# 4_Shutdown.net
KiCad netlist of a schematic drawn in Altium Designer
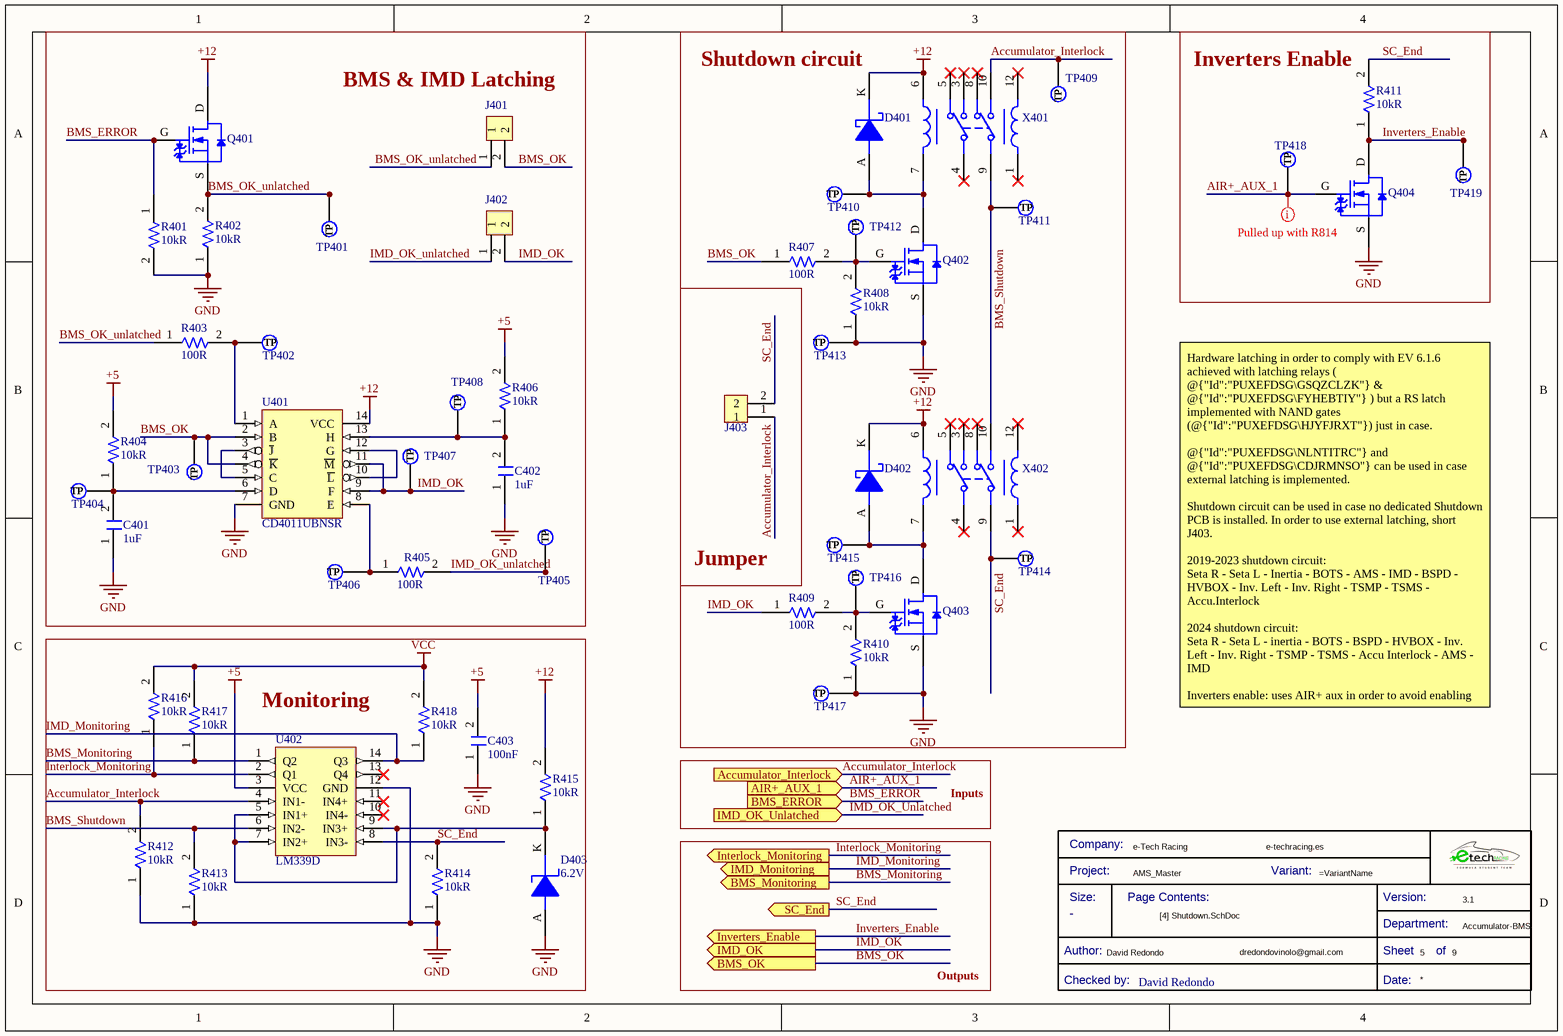
[diagram p0: [4] Shutdown.SchDoc]

(export (version "E")
  (design (tool "Eeschema 10.0.6"))
  (components
    (comp (ref "C401")
      (value "885012207103")
      (footprint "C0805FNPC-R")
      (fields
        (field (name "TOLERANCE") "10%")
        (field (name "CAPACITANCE") "1uF")
        (field (name ".CREATOR") "GP")
      )
      (libsource (lib "Passives") (part "C1u-50V-0805FNPC-X7R"))
    )
    (comp (ref "C402")
      (value "885012207103")
      (footprint "C0805FNPC-R")
      (fields
        (field (name "TOLERANCE") "10%")
        (field (name "CAPACITANCE") "1uF")
        (field (name ".CREATOR") "GP")
      )
      (libsource (lib "Passives") (part "C1u-50V-0805FNPC-X7R"))
    )
    (comp (ref "C403")
      (value "885012207098")
      (footprint "C0805FNPC-R")
      (description "Cap, 0.1ΜF, 50V, 10%, X7R, 0805")
      (fields
        (field (name "TOLERANCE") "10%")
        (field (name "CAPACITANCE") "100nF")
        (field (name ".CREATOR") "DR")
      )
      (libsource (lib "Passives") (part "C100n-50V-0805FNPC-X7R"))
    )
    (comp (ref "D401")
      (value "MBR0530")
      (footprint "DSC-SOD123")
      (description "VR=30V IF=500mA 30pF P=410mW")
      (fields (field (name ".CREATOR") "GP"))
      (libsource (lib "Filter components") (part "DSC-0.5/30-SOD123"))
    )
    (comp (ref "D402")
      (value "MBR0530")
      (footprint "DSC-SOD123")
      (description "VR=30V IF=500mA 30pF P=410mW")
      (fields (field (name ".CREATOR") "GP"))
      (libsource (lib "Filter components") (part "DSC-0.5/30-SOD123"))
    )
    (comp (ref "D403")
      (value "BZG05C6V2-E3-TR")
      (footprint "DZ-6.2V-DO-214AC")
      (description "BZG05C Series 6.2 V 200 mA Surface Mount Zener Diode - DO-214AC")
      (fields
        (field (name "TOLERANCE") "5%")
        (field (name "ZENER VOLTAGE") "6.2V")
        (field (name ".CREATOR") "DO")
      )
      (libsource (lib "Semiconductor") (part "DZ-6.2V-DO-214AC"))
    )
    (comp (ref "J401")
      (value "61300211121")
      (footprint "J_Pinheader_1x2")
      (description "CONN HEADER 2 POS 2.54")
      (fields (field (name "MANUFACTURER") "Molex") (field (name ".CREATOR") "GP"))
      (libsource (lib "Electromechanical") (part "J_Jumper"))
    )
    (comp (ref "J402")
      (value "61300211121")
      (footprint "J_Pinheader_1x2")
      (description "CONN HEADER 2 POS 2.54")
      (fields (field (name "MANUFACTURER") "Molex") (field (name ".CREATOR") "GP"))
      (libsource (lib "Electromechanical") (part "J_Jumper"))
    )
    (comp (ref "J403")
      (value "61300211121")
      (footprint "J_Pinheader_1x2")
      (description "CONN HEADER 2 POS 2.54")
      (fields (field (name "MANUFACTURER") "Molex") (field (name ".CREATOR") "GP"))
      (libsource (lib "") (part "J_Jumper_1"))
    )
    (comp (ref "Q401")
      (value "CPH3455-TL-H")
      (footprint "TRT-NCH-3/35-CPH")
      (description "CPH3455-TL-H N-channel MOSFET Transistor; 3 A; 35 V; 3-Pin CPH")
      (fields (field (name "MANUFACTURER") "ON Semiconductor") (field (name ".CREATOR") "GP"))
      (libsource (lib "Semiconductor") (part "TRT-NCH-3/35-CPH"))
    )
    (comp (ref "Q402")
      (value "CPH3455-TL-H")
      (footprint "TRT-NCH-3/35-CPH")
      (description "CPH3455-TL-H N-channel MOSFET Transistor; 3 A; 35 V; 3-Pin CPH")
      (fields (field (name "MANUFACTURER") "ON Semiconductor") (field (name ".CREATOR") "GP"))
      (libsource (lib "Semiconductor") (part "TRT-NCH-3/35-CPH"))
    )
    (comp (ref "Q403")
      (value "CPH3455-TL-H")
      (footprint "TRT-NCH-3/35-CPH")
      (description "CPH3455-TL-H N-channel MOSFET Transistor; 3 A; 35 V; 3-Pin CPH")
      (fields (field (name "MANUFACTURER") "ON Semiconductor") (field (name ".CREATOR") "GP"))
      (libsource (lib "Semiconductor") (part "TRT-NCH-3/35-CPH"))
    )
    (comp (ref "Q404")
      (value "CPH3455-TL-H")
      (footprint "TRT-NCH-3/35-CPH")
      (description "CPH3455-TL-H N-channel MOSFET Transistor; 3 A; 35 V; 3-Pin CPH")
      (fields (field (name "MANUFACTURER") "ON Semiconductor") (field (name ".CREATOR") "GP"))
      (libsource (lib "Semiconductor") (part "TRT-NCH-3/35-CPH"))
    )
    (comp (ref "R401")
      (value "CR0805-JW-103ELF")
      (footprint "R0805FTK")
      (fields
        (field (name "TOLERANCE") "5%")
        (field (name "RESISTANCE") "10kR")
        (field (name ".CREATOR") "DR")
      )
      (libsource (lib "Passives") (part "R10k-0805FTK"))
    )
    (comp (ref "R402")
      (value "CR0805-JW-103ELF")
      (footprint "R0805FTK")
      (fields
        (field (name "TOLERANCE") "5%")
        (field (name "RESISTANCE") "10kR")
        (field (name ".CREATOR") "DR")
      )
      (libsource (lib "Passives") (part "R10k-0805FTK"))
    )
    (comp (ref "R403")
      (value "CR0805-FX-1000ELF")
      (footprint "R0805FTK")
      (description "Res Thick Film 0805 100 Ohm 1% 1/8W ±100ppm/°C Molded SMD SMD Paper Tape on Plastic Reel")
      (fields
        (field (name "TOLERANCE") "1%")
        (field (name "RESISTANCE") "100R")
        (field (name ".CREATOR") "DR")
      )
      (libsource (lib "Passives") (part "R100-0805FTK"))
    )
    (comp (ref "R404")
      (value "CR0805-JW-103ELF")
      (footprint "R0805FTK")
      (fields
        (field (name "TOLERANCE") "5%")
        (field (name "RESISTANCE") "10kR")
        (field (name ".CREATOR") "DR")
      )
      (libsource (lib "Passives") (part "R10k-0805FTK"))
    )
    (comp (ref "R405")
      (value "CR0805-FX-1000ELF")
      (footprint "R0805FTK")
      (description "Res Thick Film 0805 100 Ohm 1% 1/8W ±100ppm/°C Molded SMD SMD Paper Tape on Plastic Reel")
      (fields
        (field (name "TOLERANCE") "1%")
        (field (name "RESISTANCE") "100R")
        (field (name ".CREATOR") "DR")
      )
      (libsource (lib "Passives") (part "R100-0805FTK"))
    )
    (comp (ref "R406")
      (value "CR0805-JW-103ELF")
      (footprint "R0805FTK")
      (fields
        (field (name "TOLERANCE") "5%")
        (field (name "RESISTANCE") "10kR")
        (field (name ".CREATOR") "DR")
      )
      (libsource (lib "Passives") (part "R10k-0805FTK"))
    )
    (comp (ref "R407")
      (value "CR0805-FX-1000ELF")
      (footprint "R0805FTK")
      (description "Res Thick Film 0805 100 Ohm 1% 1/8W ±100ppm/°C Molded SMD SMD Paper Tape on Plastic Reel")
      (fields
        (field (name "TOLERANCE") "1%")
        (field (name "RESISTANCE") "100R")
        (field (name ".CREATOR") "DR")
      )
      (libsource (lib "Passives") (part "R100-0805FTK"))
    )
    (comp (ref "R408")
      (value "CR0805-JW-103ELF")
      (footprint "R0805FTK")
      (fields
        (field (name "TOLERANCE") "5%")
        (field (name "RESISTANCE") "10kR")
        (field (name ".CREATOR") "DR")
      )
      (libsource (lib "Passives") (part "R10k-0805FTK"))
    )
    (comp (ref "R409")
      (value "CR0805-FX-1000ELF")
      (footprint "R0805FTK")
      (description "Res Thick Film 0805 100 Ohm 1% 1/8W ±100ppm/°C Molded SMD SMD Paper Tape on Plastic Reel")
      (fields
        (field (name "TOLERANCE") "1%")
        (field (name "RESISTANCE") "100R")
        (field (name ".CREATOR") "DR")
      )
      (libsource (lib "Passives") (part "R100-0805FTK"))
    )
    (comp (ref "R410")
      (value "CR0805-JW-103ELF")
      (footprint "R0805FTK")
      (fields
        (field (name "TOLERANCE") "5%")
        (field (name "RESISTANCE") "10kR")
        (field (name ".CREATOR") "DR")
      )
      (libsource (lib "Passives") (part "R10k-0805FTK"))
    )
    (comp (ref "R411")
      (value "CR0805-JW-103ELF")
      (footprint "R0805FTK")
      (fields
        (field (name "TOLERANCE") "5%")
        (field (name "RESISTANCE") "10kR")
        (field (name ".CREATOR") "DR")
      )
      (libsource (lib "Passives") (part "R10k-0805FTK"))
    )
    (comp (ref "R412")
      (value "CR0805-JW-103ELF")
      (footprint "R0805FTK")
      (fields
        (field (name "TOLERANCE") "5%")
        (field (name "RESISTANCE") "10kR")
        (field (name ".CREATOR") "DR")
      )
      (libsource (lib "Passives") (part "R10k-0805FTK"))
    )
    (comp (ref "R413")
      (value "CR0805-JW-103ELF")
      (footprint "R0805FTK")
      (fields
        (field (name "TOLERANCE") "5%")
        (field (name "RESISTANCE") "10kR")
        (field (name ".CREATOR") "DR")
      )
      (libsource (lib "Passives") (part "R10k-0805FTK"))
    )
    (comp (ref "R414")
      (value "CR0805-JW-103ELF")
      (footprint "R0805FTK")
      (fields
        (field (name "TOLERANCE") "5%")
        (field (name "RESISTANCE") "10kR")
        (field (name ".CREATOR") "DR")
      )
      (libsource (lib "Passives") (part "R10k-0805FTK"))
    )
    (comp (ref "R415")
      (value "CR0805-JW-103ELF")
      (footprint "R0805FTK")
      (fields
        (field (name "TOLERANCE") "5%")
        (field (name "RESISTANCE") "10kR")
        (field (name ".CREATOR") "DR")
      )
      (libsource (lib "Passives") (part "R10k-0805FTK"))
    )
    (comp (ref "R416")
      (value "CR0805-JW-103ELF")
      (footprint "R0805FTK")
      (fields
        (field (name "TOLERANCE") "5%")
        (field (name "RESISTANCE") "10kR")
        (field (name ".CREATOR") "DR")
      )
      (libsource (lib "Passives") (part "R10k-0805FTK"))
    )
    (comp (ref "R417")
      (value "CR0805-JW-103ELF")
      (footprint "R0805FTK")
      (fields
        (field (name "TOLERANCE") "5%")
        (field (name "RESISTANCE") "10kR")
        (field (name ".CREATOR") "DR")
      )
      (libsource (lib "Passives") (part "R10k-0805FTK"))
    )
    (comp (ref "R418")
      (value "CR0805-JW-103ELF")
      (footprint "R0805FTK")
      (fields
        (field (name "TOLERANCE") "5%")
        (field (name "RESISTANCE") "10kR")
        (field (name ".CREATOR") "DR")
      )
      (libsource (lib "Passives") (part "R10k-0805FTK"))
    )
    (comp (ref "TP401")
      (value "TestPoint")
      (footprint "TestPoint")
      (description "Test Point 1x1 mm")
      (fields (field (name ".CREATOR") "GP") (field (name ".PCBCHECK") "GP") (field (name ".SCHCHECK") "GP"))
      (libsource (lib "e-Tech_Racing") (part "TestPoint"))
    )
    (comp (ref "TP402")
      (value "TestPoint")
      (footprint "TestPoint")
      (description "Test Point 1x1 mm")
      (fields (field (name ".CREATOR") "GP") (field (name ".PCBCHECK") "GP") (field (name ".SCHCHECK") "GP"))
      (libsource (lib "e-Tech_Racing") (part "TestPoint"))
    )
    (comp (ref "TP403")
      (value "TestPoint")
      (footprint "TestPoint")
      (description "Test Point 1x1 mm")
      (fields (field (name ".CREATOR") "GP") (field (name ".PCBCHECK") "GP") (field (name ".SCHCHECK") "GP"))
      (libsource (lib "e-Tech_Racing") (part "TestPoint"))
    )
    (comp (ref "TP404")
      (value "TestPoint")
      (footprint "TestPoint")
      (description "Test Point 1x1 mm")
      (fields (field (name ".CREATOR") "GP") (field (name ".PCBCHECK") "GP") (field (name ".SCHCHECK") "GP"))
      (libsource (lib "e-Tech_Racing") (part "TestPoint"))
    )
    (comp (ref "TP405")
      (value "TestPoint")
      (footprint "TestPoint")
      (description "Test Point 1x1 mm")
      (fields (field (name ".CREATOR") "GP") (field (name ".PCBCHECK") "GP") (field (name ".SCHCHECK") "GP"))
      (libsource (lib "e-Tech_Racing") (part "TestPoint"))
    )
    (comp (ref "TP406")
      (value "TestPoint")
      (footprint "TestPoint")
      (description "Test Point 1x1 mm")
      (fields (field (name ".CREATOR") "GP") (field (name ".PCBCHECK") "GP") (field (name ".SCHCHECK") "GP"))
      (libsource (lib "e-Tech_Racing") (part "TestPoint"))
    )
    (comp (ref "TP407")
      (value "TestPoint")
      (footprint "TestPoint")
      (description "Test Point 1x1 mm")
      (fields (field (name ".CREATOR") "GP") (field (name ".PCBCHECK") "GP") (field (name ".SCHCHECK") "GP"))
      (libsource (lib "e-Tech_Racing") (part "TestPoint"))
    )
    (comp (ref "TP408")
      (value "TestPoint")
      (footprint "TestPoint")
      (description "Test Point 1x1 mm")
      (fields (field (name ".CREATOR") "GP") (field (name ".PCBCHECK") "GP") (field (name ".SCHCHECK") "GP"))
      (libsource (lib "e-Tech_Racing") (part "TestPoint"))
    )
    (comp (ref "TP409")
      (value "TestPoint")
      (footprint "TestPoint")
      (description "Test Point 1x1 mm")
      (fields (field (name ".CREATOR") "GP") (field (name ".PCBCHECK") "GP") (field (name ".SCHCHECK") "GP"))
      (libsource (lib "e-Tech_Racing") (part "TestPoint"))
    )
    (comp (ref "TP410")
      (value "TestPoint")
      (footprint "TestPoint")
      (description "Test Point 1x1 mm")
      (fields (field (name ".CREATOR") "GP") (field (name ".PCBCHECK") "GP") (field (name ".SCHCHECK") "GP"))
      (libsource (lib "e-Tech_Racing") (part "TestPoint"))
    )
    (comp (ref "TP411")
      (value "TestPoint")
      (footprint "TestPoint")
      (description "Test Point 1x1 mm")
      (fields (field (name ".CREATOR") "GP") (field (name ".PCBCHECK") "GP") (field (name ".SCHCHECK") "GP"))
      (libsource (lib "e-Tech_Racing") (part "TestPoint"))
    )
    (comp (ref "TP412")
      (value "TestPoint")
      (footprint "TestPoint")
      (description "Test Point 1x1 mm")
      (fields (field (name ".CREATOR") "GP") (field (name ".PCBCHECK") "GP") (field (name ".SCHCHECK") "GP"))
      (libsource (lib "e-Tech_Racing") (part "TestPoint"))
    )
    (comp (ref "TP413")
      (value "TestPoint")
      (footprint "TestPoint")
      (description "Test Point 1x1 mm")
      (fields (field (name ".CREATOR") "GP") (field (name ".PCBCHECK") "GP") (field (name ".SCHCHECK") "GP"))
      (libsource (lib "e-Tech_Racing") (part "TestPoint"))
    )
    (comp (ref "TP414")
      (value "TestPoint")
      (footprint "TestPoint")
      (description "Test Point 1x1 mm")
      (fields (field (name ".CREATOR") "GP") (field (name ".PCBCHECK") "GP") (field (name ".SCHCHECK") "GP"))
      (libsource (lib "e-Tech_Racing") (part "TestPoint"))
    )
    (comp (ref "TP415")
      (value "TestPoint")
      (footprint "TestPoint")
      (description "Test Point 1x1 mm")
      (fields (field (name ".CREATOR") "GP") (field (name ".PCBCHECK") "GP") (field (name ".SCHCHECK") "GP"))
      (libsource (lib "e-Tech_Racing") (part "TestPoint"))
    )
    (comp (ref "TP416")
      (value "TestPoint")
      (footprint "TestPoint")
      (description "Test Point 1x1 mm")
      (fields (field (name ".CREATOR") "GP") (field (name ".PCBCHECK") "GP") (field (name ".SCHCHECK") "GP"))
      (libsource (lib "e-Tech_Racing") (part "TestPoint"))
    )
    (comp (ref "TP417")
      (value "TestPoint")
      (footprint "TestPoint")
      (description "Test Point 1x1 mm")
      (fields (field (name ".CREATOR") "GP") (field (name ".PCBCHECK") "GP") (field (name ".SCHCHECK") "GP"))
      (libsource (lib "e-Tech_Racing") (part "TestPoint"))
    )
    (comp (ref "TP418")
      (value "TestPoint")
      (footprint "TestPoint")
      (description "Test Point 1x1 mm")
      (fields (field (name ".CREATOR") "GP") (field (name ".PCBCHECK") "GP") (field (name ".SCHCHECK") "GP"))
      (libsource (lib "e-Tech_Racing") (part "TestPoint"))
    )
    (comp (ref "TP419")
      (value "TestPoint")
      (footprint "TestPoint")
      (description "Test Point 1x1 mm")
      (fields (field (name ".CREATOR") "GP") (field (name ".PCBCHECK") "GP") (field (name ".SCHCHECK") "GP"))
      (libsource (lib "e-Tech_Racing") (part "TestPoint"))
    )
    (comp (ref "U401")
      (value "CD4011UBSNR")
      (footprint "ARRAY_4_NAND")
      (description "CD4011UB Cmos Quad 2-INPUT Nand")
      (fields
        (field (name "MANUFACTURER") "Texas Instruments")
        (field (name "MANUFACTURER PART NUMBER") "CD4011UBNSR")
        (field (name ".CREATOR") "DO")
      )
      (libsource (lib "Integrated circuits") (part "Array_4_NAND"))
    )
    (comp (ref "U402")
      (value "LM339D")
      (footprint "Array_4_Amp_LM339D")
      (description "Comparator Quad ±18V/36V 14-Pin SOIC Tube")
      (fields
        (field (name "MANUFACTURER") "Texas Instruments")
        (field (name "MANUFACTURER PART NUMBER") "LM339D")
        (field (name ".CREATOR") "DO")
      )
      (libsource (lib "Integrated circuits") (part "Array_4_Amp_LM339D"))
    )
    (comp (ref "X401")
      (value "Relay_V23079")
      (footprint "Relay_V23079")
      (description "Electromechanical Relay 5VDC 178Ohm 2A DPDT (14.5x7.2x9.8)mm THT Signal Relay")
      (libsource (lib "Electromechanical") (part "Relay_V23079"))
    )
    (comp (ref "X402")
      (value "Relay_V23079")
      (footprint "Relay_V23079")
      (description "Electromechanical Relay 5VDC 178Ohm 2A DPDT (14.5x7.2x9.8)mm THT Signal Relay")
      (libsource (lib "Electromechanical") (part "Relay_V23079"))
    )
  )
  (nets
    (net (code "1") (name "+5") (class "Default")
      (node (ref "C403") (pin "2") (pinfunction "2_2") (pintype "passive"))
      (node (ref "R404") (pin "2") (pinfunction "2_2") (pintype "passive"))
      (node (ref "R406") (pin "2") (pinfunction "2_2") (pintype "passive"))
      (node (ref "U402") (pin "3") (pinfunction "VCC_3") (pintype "power_in"))
    )
    (net (code "2") (name "+12") (class "Default")
      (node (ref "D401") (pin "K") (pinfunction "K_K") (pintype "passive"))
      (node (ref "D402") (pin "K") (pinfunction "K_K") (pintype "passive"))
      (node (ref "Q401") (pin "D") (pinfunction "D_D") (pintype "passive"))
      (node (ref "R415") (pin "2") (pinfunction "2_2") (pintype "passive"))
      (node (ref "U401") (pin "14") (pinfunction "VCC_14") (pintype "power_in"))
      (node (ref "X401") (pin "6") (pinfunction "6_6") (pintype "passive"))
      (node (ref "X402") (pin "6") (pinfunction "6_6") (pintype "passive"))
    )
    (net (code "3") (name "/AIR+_AUX_1") (class "Default")
      (node (ref "Q404") (pin "G") (pinfunction "G_G") (pintype "passive"))
      (node (ref "TP418") (pin "1") (pinfunction "TP_1") (pintype "passive"))
    )
    (net (code "4") (name "/Accumulator_Interlock") (class "Default")
      (node (ref "J403") (pin "1") (pinfunction "1_1") (pintype "passive"))
      (node (ref "R412") (pin "2") (pinfunction "2_2") (pintype "passive"))
      (node (ref "TP409") (pin "1") (pinfunction "TP_1") (pintype "passive"))
      (node (ref "U402") (pin "4") (pinfunction "IN1-_4") (pintype "input"))
      (node (ref "X401") (pin "10") (pinfunction "10_10") (pintype "passive"))
    )
    (net (code "5") (name "/BMS_ERROR") (class "Default")
      (node (ref "Q401") (pin "G") (pinfunction "G_G") (pintype "passive"))
      (node (ref "R401") (pin "1") (pinfunction "1_1") (pintype "passive"))
    )
    (net (code "6") (name "/BMS_Monitoring") (class "Default")
      (node (ref "R417") (pin "1") (pinfunction "1_1") (pintype "passive"))
      (node (ref "U402") (pin "1") (pinfunction "Q2_1") (pintype "output"))
    )
    (net (code "7") (name "/BMS_OK") (class "Default")
      (node (ref "J401") (pin "2") (pinfunction "2_2") (pintype "passive"))
      (node (ref "R407") (pin "1") (pinfunction "1_1") (pintype "passive"))
      (node (ref "TP403") (pin "1") (pinfunction "TP_1") (pintype "passive"))
      (node (ref "U401") (pin "2") (pinfunction "B_2") (pintype "input"))
      (node (ref "U401") (pin "4") (pinfunction "~{K}_4") (pintype "output"))
    )
    (net (code "8") (name "/BMS_OK_unlatched") (class "Default")
      (node (ref "J401") (pin "1") (pinfunction "1_1") (pintype "passive"))
      (node (ref "Q401") (pin "S") (pinfunction "S_S") (pintype "passive"))
      (node (ref "R402") (pin "2") (pinfunction "2_2") (pintype "passive"))
      (node (ref "R403") (pin "1") (pinfunction "1_1") (pintype "passive"))
      (node (ref "TP401") (pin "1") (pinfunction "TP_1") (pintype "passive"))
    )
    (net (code "9") (name "/BMS_Shutdown") (class "Default")
      (node (ref "R413") (pin "2") (pinfunction "2_2") (pintype "passive"))
      (node (ref "TP411") (pin "1") (pinfunction "TP_1") (pintype "passive"))
      (node (ref "U402") (pin "6") (pinfunction "IN2-_6") (pintype "input"))
      (node (ref "X401") (pin "9") (pinfunction "9_9") (pintype "passive"))
      (node (ref "X402") (pin "10") (pinfunction "10_10") (pintype "passive"))
    )
    (net (code "10") (name "/IMD_Monitoring") (class "Default")
      (node (ref "R418") (pin "1") (pinfunction "1_1") (pintype "passive"))
      (node (ref "U402") (pin "14") (pinfunction "Q3_14") (pintype "output"))
    )
    (net (code "11") (name "/IMD_OK") (class "Default")
      (node (ref "J402") (pin "2") (pinfunction "2_2") (pintype "passive"))
      (node (ref "R409") (pin "1") (pinfunction "1_1") (pintype "passive"))
      (node (ref "TP407") (pin "1") (pinfunction "TP_1") (pintype "passive"))
      (node (ref "U401") (pin "11") (pinfunction "~{M}_11") (pintype "output"))
      (node (ref "U401") (pin "9") (pinfunction "F_9") (pintype "input"))
    )
    (net (code "13") (name "/IMD_OK_unlatched") (class "Default")
      (node (ref "J402") (pin "1") (pinfunction "1_1") (pintype "passive"))
      (node (ref "R405") (pin "2") (pinfunction "2_2") (pintype "passive"))
      (node (ref "TP405") (pin "1") (pinfunction "TP_1") (pintype "passive"))
    )
    (net (code "14") (name "/Interlock_Monitoring") (class "Default")
      (node (ref "R416") (pin "1") (pinfunction "1_1") (pintype "passive"))
      (node (ref "U402") (pin "2") (pinfunction "Q1_2") (pintype "output"))
    )
    (net (code "15") (name "/Inverters_Enable") (class "Default")
      (node (ref "Q404") (pin "D") (pinfunction "D_D") (pintype "passive"))
      (node (ref "R411") (pin "1") (pinfunction "1_1") (pintype "passive"))
      (node (ref "TP419") (pin "1") (pinfunction "TP_1") (pintype "passive"))
    )
    (net (code "16") (name "/SC_End") (class "Default")
      (node (ref "J403") (pin "2") (pinfunction "2_2") (pintype "passive"))
      (node (ref "R411") (pin "2") (pinfunction "2_2") (pintype "passive"))
      (node (ref "R414") (pin "2") (pinfunction "2_2") (pintype "passive"))
      (node (ref "TP414") (pin "1") (pinfunction "TP_1") (pintype "passive"))
      (node (ref "U402") (pin "8") (pinfunction "IN3-_8") (pintype "input"))
      (node (ref "X402") (pin "9") (pinfunction "9_9") (pintype "passive"))
    )
    (net (code "17") (name "GND") (class "Default")
      (node (ref "C401") (pin "1") (pinfunction "1_1") (pintype "passive"))
      (node (ref "C402") (pin "1") (pinfunction "1_1") (pintype "passive"))
      (node (ref "C403") (pin "1") (pinfunction "1_1") (pintype "passive"))
      (node (ref "D403") (pin "A") (pinfunction "A_A") (pintype "passive"))
      (node (ref "Q402") (pin "S") (pinfunction "S_S") (pintype "passive"))
      (node (ref "Q403") (pin "S") (pinfunction "S_S") (pintype "passive"))
      (node (ref "Q404") (pin "S") (pinfunction "S_S") (pintype "passive"))
      (node (ref "R401") (pin "2") (pinfunction "2_2") (pintype "passive"))
      (node (ref "R402") (pin "1") (pinfunction "1_1") (pintype "passive"))
      (node (ref "R408") (pin "1") (pinfunction "1_1") (pintype "passive"))
      (node (ref "R410") (pin "1") (pinfunction "1_1") (pintype "passive"))
      (node (ref "R412") (pin "1") (pinfunction "1_1") (pintype "passive"))
      (node (ref "R413") (pin "1") (pinfunction "1_1") (pintype "passive"))
      (node (ref "R414") (pin "1") (pinfunction "1_1") (pintype "passive"))
      (node (ref "TP413") (pin "1") (pinfunction "TP_1") (pintype "passive"))
      (node (ref "TP417") (pin "1") (pinfunction "TP_1") (pintype "passive"))
      (node (ref "U401") (pin "7") (pinfunction "GND_7") (pintype "power_in"))
      (node (ref "U402") (pin "12") (pinfunction "GND_12") (pintype "power_in"))
    )
    (net (code "18") (name "Net-(TP402-TP)") (class "Default")
      (node (ref "R403") (pin "2") (pinfunction "2_2") (pintype "passive"))
      (node (ref "TP402") (pin "1") (pinfunction "TP_1") (pintype "passive"))
      (node (ref "U401") (pin "1") (pinfunction "A_1") (pintype "input"))
    )
    (net (code "19") (name "Net-(TP404-TP)") (class "Default")
      (node (ref "C401") (pin "2") (pinfunction "2_2") (pintype "passive"))
      (node (ref "R404") (pin "1") (pinfunction "1_1") (pintype "passive"))
      (node (ref "TP404") (pin "1") (pinfunction "TP_1") (pintype "passive"))
      (node (ref "U401") (pin "6") (pinfunction "D_6") (pintype "input"))
    )
    (net (code "20") (name "Net-(TP406-TP)") (class "Default")
      (node (ref "R405") (pin "1") (pinfunction "1_1") (pintype "passive"))
      (node (ref "TP406") (pin "1") (pinfunction "TP_1") (pintype "passive"))
      (node (ref "U401") (pin "8") (pinfunction "E_8") (pintype "input"))
    )
    (net (code "21") (name "Net-(TP408-TP)") (class "Default")
      (node (ref "C402") (pin "2") (pinfunction "2_2") (pintype "passive"))
      (node (ref "R406") (pin "1") (pinfunction "1_1") (pintype "passive"))
      (node (ref "TP408") (pin "1") (pinfunction "TP_1") (pintype "passive"))
      (node (ref "U401") (pin "13") (pinfunction "H_13") (pintype "input"))
    )
    (net (code "22") (name "Net-(TP410-TP)") (class "Default")
      (node (ref "D401") (pin "A") (pinfunction "A_A") (pintype "passive"))
      (node (ref "Q402") (pin "D") (pinfunction "D_D") (pintype "passive"))
      (node (ref "TP410") (pin "1") (pinfunction "TP_1") (pintype "passive"))
      (node (ref "X401") (pin "7") (pinfunction "7_7") (pintype "passive"))
    )
    (net (code "23") (name "Net-(TP412-TP)") (class "Default")
      (node (ref "Q402") (pin "G") (pinfunction "G_G") (pintype "passive"))
      (node (ref "R407") (pin "2") (pinfunction "2_2") (pintype "passive"))
      (node (ref "R408") (pin "2") (pinfunction "2_2") (pintype "passive"))
      (node (ref "TP412") (pin "1") (pinfunction "TP_1") (pintype "passive"))
    )
    (net (code "24") (name "Net-(TP415-TP)") (class "Default")
      (node (ref "D402") (pin "A") (pinfunction "A_A") (pintype "passive"))
      (node (ref "Q403") (pin "D") (pinfunction "D_D") (pintype "passive"))
      (node (ref "TP415") (pin "1") (pinfunction "TP_1") (pintype "passive"))
      (node (ref "X402") (pin "7") (pinfunction "7_7") (pintype "passive"))
    )
    (net (code "25") (name "Net-(TP416-TP)") (class "Default")
      (node (ref "Q403") (pin "G") (pinfunction "G_G") (pintype "passive"))
      (node (ref "R409") (pin "2") (pinfunction "2_2") (pintype "passive"))
      (node (ref "R410") (pin "2") (pinfunction "2_2") (pintype "passive"))
      (node (ref "TP416") (pin "1") (pinfunction "TP_1") (pintype "passive"))
    )
    (net (code "26") (name "Net-(U401-C)") (class "Default")
      (node (ref "U401") (pin "3") (pinfunction "~{J}_3") (pintype "output"))
      (node (ref "U401") (pin "5") (pinfunction "C_5") (pintype "input"))
    )
    (net (code "27") (name "Net-(U401-G)") (class "Default")
      (node (ref "U401") (pin "10") (pinfunction "~{L}_10") (pintype "output"))
      (node (ref "U401") (pin "12") (pinfunction "G_12") (pintype "input"))
    )
    (net (code "28") (name "Net-(U402-IN1+)") (class "Default")
      (node (ref "D403") (pin "K") (pinfunction "K_K") (pintype "passive"))
      (node (ref "R415") (pin "1") (pinfunction "1_1") (pintype "passive"))
      (node (ref "U402") (pin "5") (pinfunction "IN1+_5") (pintype "input"))
      (node (ref "U402") (pin "7") (pinfunction "IN2+_7") (pintype "input"))
      (node (ref "U402") (pin "9") (pinfunction "IN3+_9") (pintype "input"))
    )
    (net (code "29") (name "VCC") (class "Default")
      (node (ref "R416") (pin "2") (pinfunction "2_2") (pintype "passive"))
      (node (ref "R417") (pin "2") (pinfunction "2_2") (pintype "passive"))
      (node (ref "R418") (pin "2") (pinfunction "2_2") (pintype "passive"))
    )
    (net (code "30") (name "unconnected-(U402-IN4+-Pad11)") (class "Default")
      (node (ref "U402") (pin "11") (pinfunction "IN4+_11") (pintype "input+no_connect"))
    )
    (net (code "31") (name "unconnected-(U402-IN4--Pad10)") (class "Default")
      (node (ref "U402") (pin "10") (pinfunction "IN4-_10") (pintype "input+no_connect"))
    )
    (net (code "32") (name "unconnected-(U402-Q4-Pad13)") (class "Default")
      (node (ref "U402") (pin "13") (pinfunction "Q4_13") (pintype "output+no_connect"))
    )
    (net (code "33") (name "unconnected-(X401-Pad1)") (class "Default")
      (node (ref "X401") (pin "1") (pinfunction "1_1") (pintype "passive+no_connect"))
    )
    (net (code "34") (name "unconnected-(X401-Pad3)") (class "Default")
      (node (ref "X401") (pin "3") (pinfunction "3_3") (pintype "passive+no_connect"))
    )
    (net (code "35") (name "unconnected-(X401-Pad4)") (class "Default")
      (node (ref "X401") (pin "4") (pinfunction "4_4") (pintype "passive+no_connect"))
    )
    (net (code "36") (name "unconnected-(X401-Pad5)") (class "Default")
      (node (ref "X401") (pin "5") (pinfunction "5_5") (pintype "passive+no_connect"))
    )
    (net (code "37") (name "unconnected-(X401-Pad8)") (class "Default")
      (node (ref "X401") (pin "8") (pinfunction "8_8") (pintype "passive+no_connect"))
    )
    (net (code "38") (name "unconnected-(X401-Pad12)") (class "Default")
      (node (ref "X401") (pin "12") (pinfunction "12_12") (pintype "passive+no_connect"))
    )
    (net (code "39") (name "unconnected-(X402-Pad1)") (class "Default")
      (node (ref "X402") (pin "1") (pinfunction "1_1") (pintype "passive+no_connect"))
    )
    (net (code "40") (name "unconnected-(X402-Pad3)") (class "Default")
      (node (ref "X402") (pin "3") (pinfunction "3_3") (pintype "passive+no_connect"))
    )
    (net (code "41") (name "unconnected-(X402-Pad4)") (class "Default")
      (node (ref "X402") (pin "4") (pinfunction "4_4") (pintype "passive+no_connect"))
    )
    (net (code "42") (name "unconnected-(X402-Pad5)") (class "Default")
      (node (ref "X402") (pin "5") (pinfunction "5_5") (pintype "passive+no_connect"))
    )
    (net (code "43") (name "unconnected-(X402-Pad8)") (class "Default")
      (node (ref "X402") (pin "8") (pinfunction "8_8") (pintype "passive+no_connect"))
    )
    (net (code "44") (name "unconnected-(X402-Pad12)") (class "Default")
      (node (ref "X402") (pin "12") (pinfunction "12_12") (pintype "passive+no_connect"))
    )
  )
)
